# fpc_cable_all.net
KiCad netlist of a schematic drawn in EAGLE
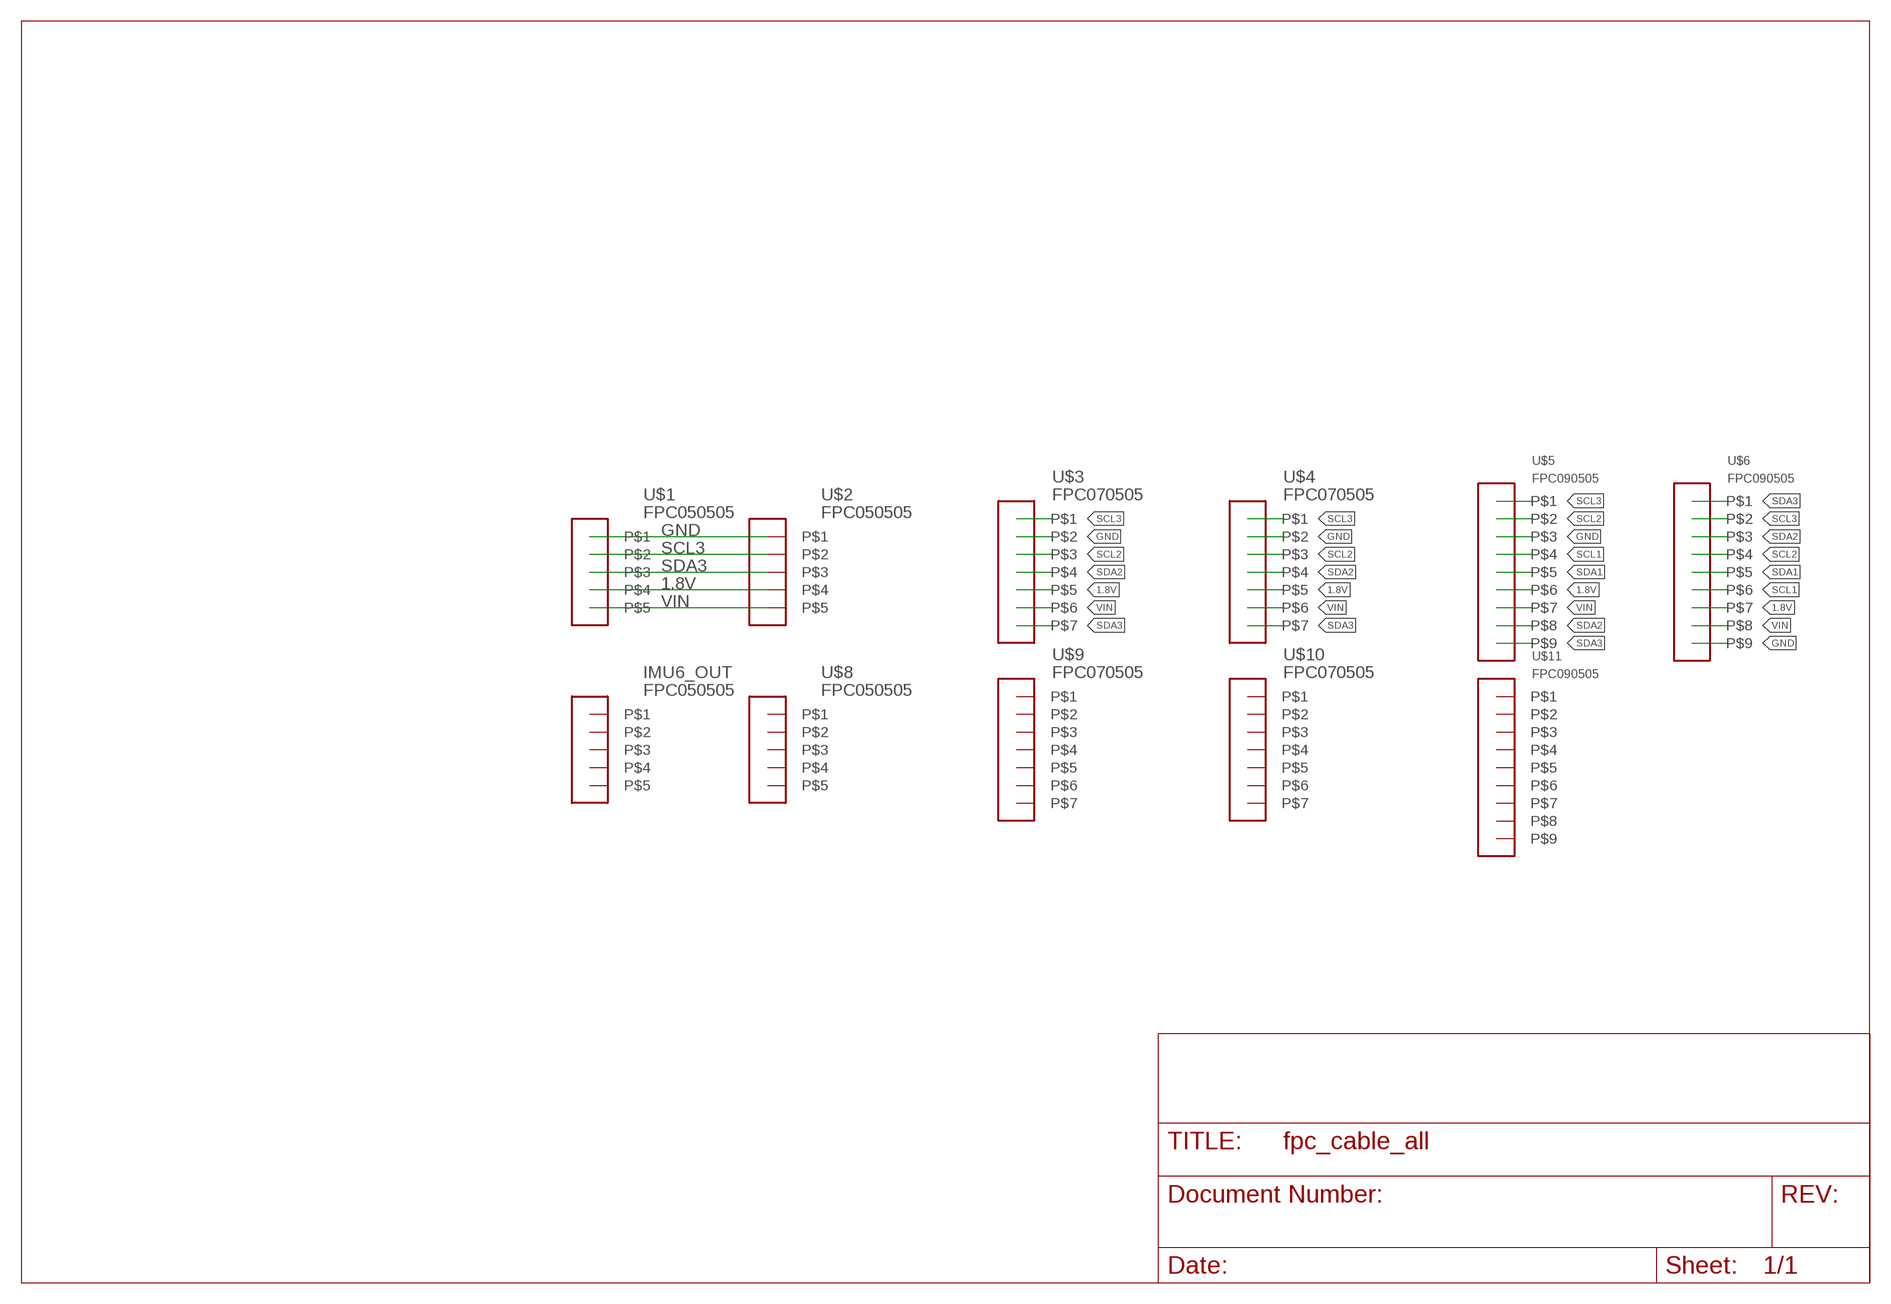
[diagram p0: schematic, sheet 1]

(export (version "E")
  (design (tool "Eeschema 10.0.6"))
  (components
    (comp (ref "IMU6_OUT")
      (value "FPC050505")
      (footprint "eagle-import:FPC0505")
      (libsource (lib "eagle-import") (part "FPC050505"))
    )
    (comp (ref "U$1")
      (value "FPC050505")
      (footprint "eagle-import:FPC0505")
      (libsource (lib "eagle-import") (part "FPC050505"))
    )
    (comp (ref "U$2")
      (value "FPC050505")
      (footprint "eagle-import:FPC0505")
      (libsource (lib "eagle-import") (part "FPC050505"))
    )
    (comp (ref "U$3")
      (value "FPC070505")
      (footprint "eagle-import:FPC0705")
      (libsource (lib "eagle-import") (part "FPC070505"))
    )
    (comp (ref "U$4")
      (value "FPC070505")
      (footprint "eagle-import:FPC0705")
      (libsource (lib "eagle-import") (part "FPC070505"))
    )
    (comp (ref "U$5")
      (value "FPC090505")
      (footprint "eagle-import:FPC0905")
      (libsource (lib "eagle-import") (part "FPC090505"))
    )
    (comp (ref "U$6")
      (value "FPC090505")
      (footprint "eagle-import:FPC0905")
      (libsource (lib "eagle-import") (part "FPC090505"))
    )
    (comp (ref "U$8")
      (value "FPC050505")
      (footprint "eagle-import:FPC0505")
      (libsource (lib "eagle-import") (part "FPC050505"))
    )
    (comp (ref "U$9")
      (value "FPC070505")
      (footprint "eagle-import:FPC0705")
      (libsource (lib "eagle-import") (part "FPC070505"))
    )
    (comp (ref "U$10")
      (value "FPC070505")
      (footprint "eagle-import:FPC0705")
      (libsource (lib "eagle-import") (part "FPC070505"))
    )
    (comp (ref "U$11")
      (value "FPC090505")
      (footprint "eagle-import:FPC0905")
      (libsource (lib "eagle-import") (part "FPC090505"))
    )
  )
  (nets
    (net (code "1") (name "1.8V") (class "Default")
      (node (ref "U$1") (pin "P$4") (pinfunction "P$4_P$4") (pintype "bidirectional"))
      (node (ref "U$2") (pin "P$4") (pinfunction "P$4_P$4") (pintype "bidirectional"))
      (node (ref "U$3") (pin "P$5") (pinfunction "P$5_P$5") (pintype "bidirectional"))
      (node (ref "U$4") (pin "P$5") (pinfunction "P$5_P$5") (pintype "bidirectional"))
      (node (ref "U$5") (pin "P$6") (pinfunction "P$6_P$6") (pintype "bidirectional"))
      (node (ref "U$6") (pin "P$7") (pinfunction "P$7_P$7") (pintype "bidirectional"))
    )
    (net (code "2") (name "GND") (class "Default")
      (node (ref "U$1") (pin "P$1") (pinfunction "P$1_P$1") (pintype "bidirectional"))
      (node (ref "U$2") (pin "P$1") (pinfunction "P$1_P$1") (pintype "bidirectional"))
      (node (ref "U$3") (pin "P$2") (pinfunction "P$2_P$2") (pintype "bidirectional"))
      (node (ref "U$4") (pin "P$2") (pinfunction "P$2_P$2") (pintype "bidirectional"))
      (node (ref "U$5") (pin "P$3") (pinfunction "P$3_P$3") (pintype "bidirectional"))
      (node (ref "U$6") (pin "P$9") (pinfunction "P$9_P$9") (pintype "bidirectional"))
    )
    (net (code "3") (name "SCL1") (class "Default")
      (node (ref "U$5") (pin "P$4") (pinfunction "P$4_P$4") (pintype "bidirectional"))
      (node (ref "U$6") (pin "P$6") (pinfunction "P$6_P$6") (pintype "bidirectional"))
    )
    (net (code "4") (name "SCL2") (class "Default")
      (node (ref "U$3") (pin "P$3") (pinfunction "P$3_P$3") (pintype "bidirectional"))
      (node (ref "U$4") (pin "P$3") (pinfunction "P$3_P$3") (pintype "bidirectional"))
      (node (ref "U$5") (pin "P$2") (pinfunction "P$2_P$2") (pintype "bidirectional"))
      (node (ref "U$6") (pin "P$4") (pinfunction "P$4_P$4") (pintype "bidirectional"))
    )
    (net (code "5") (name "SCL3") (class "Default")
      (node (ref "U$1") (pin "P$2") (pinfunction "P$2_P$2") (pintype "bidirectional"))
      (node (ref "U$2") (pin "P$2") (pinfunction "P$2_P$2") (pintype "bidirectional"))
      (node (ref "U$3") (pin "P$1") (pinfunction "P$1_P$1") (pintype "bidirectional"))
      (node (ref "U$4") (pin "P$1") (pinfunction "P$1_P$1") (pintype "bidirectional"))
      (node (ref "U$5") (pin "P$1") (pinfunction "P$1_P$1") (pintype "bidirectional"))
      (node (ref "U$6") (pin "P$2") (pinfunction "P$2_P$2") (pintype "bidirectional"))
    )
    (net (code "6") (name "SDA1") (class "Default")
      (node (ref "U$5") (pin "P$5") (pinfunction "P$5_P$5") (pintype "bidirectional"))
      (node (ref "U$6") (pin "P$5") (pinfunction "P$5_P$5") (pintype "bidirectional"))
    )
    (net (code "7") (name "SDA2") (class "Default")
      (node (ref "U$3") (pin "P$4") (pinfunction "P$4_P$4") (pintype "bidirectional"))
      (node (ref "U$4") (pin "P$4") (pinfunction "P$4_P$4") (pintype "bidirectional"))
      (node (ref "U$5") (pin "P$8") (pinfunction "P$8_P$8") (pintype "bidirectional"))
      (node (ref "U$6") (pin "P$3") (pinfunction "P$3_P$3") (pintype "bidirectional"))
    )
    (net (code "8") (name "SDA3") (class "Default")
      (node (ref "U$1") (pin "P$3") (pinfunction "P$3_P$3") (pintype "bidirectional"))
      (node (ref "U$2") (pin "P$3") (pinfunction "P$3_P$3") (pintype "bidirectional"))
      (node (ref "U$3") (pin "P$7") (pinfunction "P$7_P$7") (pintype "bidirectional"))
      (node (ref "U$4") (pin "P$7") (pinfunction "P$7_P$7") (pintype "bidirectional"))
      (node (ref "U$5") (pin "P$9") (pinfunction "P$9_P$9") (pintype "bidirectional"))
      (node (ref "U$6") (pin "P$1") (pinfunction "P$1_P$1") (pintype "bidirectional"))
    )
    (net (code "9") (name "VIN") (class "Default")
      (node (ref "U$1") (pin "P$5") (pinfunction "P$5_P$5") (pintype "bidirectional"))
      (node (ref "U$2") (pin "P$5") (pinfunction "P$5_P$5") (pintype "bidirectional"))
      (node (ref "U$3") (pin "P$6") (pinfunction "P$6_P$6") (pintype "bidirectional"))
      (node (ref "U$4") (pin "P$6") (pinfunction "P$6_P$6") (pintype "bidirectional"))
      (node (ref "U$5") (pin "P$7") (pinfunction "P$7_P$7") (pintype "bidirectional"))
      (node (ref "U$6") (pin "P$8") (pinfunction "P$8_P$8") (pintype "bidirectional"))
    )
    (net (code "10") (name "unconnected-(IMU6_OUT-PadP$1)") (class "Default")
      (node (ref "IMU6_OUT") (pin "P$1") (pinfunction "P$1_P$1") (pintype "bidirectional"))
    )
    (net (code "11") (name "unconnected-(IMU6_OUT-PadP$2)") (class "Default")
      (node (ref "IMU6_OUT") (pin "P$2") (pinfunction "P$2_P$2") (pintype "bidirectional"))
    )
    (net (code "12") (name "unconnected-(IMU6_OUT-PadP$3)") (class "Default")
      (node (ref "IMU6_OUT") (pin "P$3") (pinfunction "P$3_P$3") (pintype "bidirectional"))
    )
    (net (code "13") (name "unconnected-(IMU6_OUT-PadP$4)") (class "Default")
      (node (ref "IMU6_OUT") (pin "P$4") (pinfunction "P$4_P$4") (pintype "bidirectional"))
    )
    (net (code "14") (name "unconnected-(IMU6_OUT-PadP$5)") (class "Default")
      (node (ref "IMU6_OUT") (pin "P$5") (pinfunction "P$5_P$5") (pintype "bidirectional"))
    )
    (net (code "15") (name "unconnected-(U$8-PadP$1)") (class "Default")
      (node (ref "U$8") (pin "P$1") (pinfunction "P$1_P$1") (pintype "bidirectional"))
    )
    (net (code "16") (name "unconnected-(U$8-PadP$2)") (class "Default")
      (node (ref "U$8") (pin "P$2") (pinfunction "P$2_P$2") (pintype "bidirectional"))
    )
    (net (code "17") (name "unconnected-(U$8-PadP$3)") (class "Default")
      (node (ref "U$8") (pin "P$3") (pinfunction "P$3_P$3") (pintype "bidirectional"))
    )
    (net (code "18") (name "unconnected-(U$8-PadP$4)") (class "Default")
      (node (ref "U$8") (pin "P$4") (pinfunction "P$4_P$4") (pintype "bidirectional"))
    )
    (net (code "19") (name "unconnected-(U$8-PadP$5)") (class "Default")
      (node (ref "U$8") (pin "P$5") (pinfunction "P$5_P$5") (pintype "bidirectional"))
    )
    (net (code "20") (name "unconnected-(U$9-PadP$1)") (class "Default")
      (node (ref "U$9") (pin "P$1") (pinfunction "P$1_P$1") (pintype "bidirectional"))
    )
    (net (code "21") (name "unconnected-(U$9-PadP$2)") (class "Default")
      (node (ref "U$9") (pin "P$2") (pinfunction "P$2_P$2") (pintype "bidirectional"))
    )
    (net (code "22") (name "unconnected-(U$9-PadP$3)") (class "Default")
      (node (ref "U$9") (pin "P$3") (pinfunction "P$3_P$3") (pintype "bidirectional"))
    )
    (net (code "23") (name "unconnected-(U$9-PadP$4)") (class "Default")
      (node (ref "U$9") (pin "P$4") (pinfunction "P$4_P$4") (pintype "bidirectional"))
    )
    (net (code "24") (name "unconnected-(U$9-PadP$5)") (class "Default")
      (node (ref "U$9") (pin "P$5") (pinfunction "P$5_P$5") (pintype "bidirectional"))
    )
    (net (code "25") (name "unconnected-(U$9-PadP$6)") (class "Default")
      (node (ref "U$9") (pin "P$6") (pinfunction "P$6_P$6") (pintype "bidirectional"))
    )
    (net (code "26") (name "unconnected-(U$9-PadP$7)") (class "Default")
      (node (ref "U$9") (pin "P$7") (pinfunction "P$7_P$7") (pintype "bidirectional"))
    )
    (net (code "27") (name "unconnected-(U$10-PadP$1)") (class "Default")
      (node (ref "U$10") (pin "P$1") (pinfunction "P$1_P$1") (pintype "bidirectional"))
    )
    (net (code "28") (name "unconnected-(U$10-PadP$2)") (class "Default")
      (node (ref "U$10") (pin "P$2") (pinfunction "P$2_P$2") (pintype "bidirectional"))
    )
    (net (code "29") (name "unconnected-(U$10-PadP$3)") (class "Default")
      (node (ref "U$10") (pin "P$3") (pinfunction "P$3_P$3") (pintype "bidirectional"))
    )
    (net (code "30") (name "unconnected-(U$10-PadP$4)") (class "Default")
      (node (ref "U$10") (pin "P$4") (pinfunction "P$4_P$4") (pintype "bidirectional"))
    )
    (net (code "31") (name "unconnected-(U$10-PadP$5)") (class "Default")
      (node (ref "U$10") (pin "P$5") (pinfunction "P$5_P$5") (pintype "bidirectional"))
    )
    (net (code "32") (name "unconnected-(U$10-PadP$6)") (class "Default")
      (node (ref "U$10") (pin "P$6") (pinfunction "P$6_P$6") (pintype "bidirectional"))
    )
    (net (code "33") (name "unconnected-(U$10-PadP$7)") (class "Default")
      (node (ref "U$10") (pin "P$7") (pinfunction "P$7_P$7") (pintype "bidirectional"))
    )
    (net (code "34") (name "unconnected-(U$11-PadP$1)") (class "Default")
      (node (ref "U$11") (pin "P$1") (pinfunction "P$1_P$1") (pintype "bidirectional"))
    )
    (net (code "35") (name "unconnected-(U$11-PadP$2)") (class "Default")
      (node (ref "U$11") (pin "P$2") (pinfunction "P$2_P$2") (pintype "bidirectional"))
    )
    (net (code "36") (name "unconnected-(U$11-PadP$3)") (class "Default")
      (node (ref "U$11") (pin "P$3") (pinfunction "P$3_P$3") (pintype "bidirectional"))
    )
    (net (code "37") (name "unconnected-(U$11-PadP$4)") (class "Default")
      (node (ref "U$11") (pin "P$4") (pinfunction "P$4_P$4") (pintype "bidirectional"))
    )
    (net (code "38") (name "unconnected-(U$11-PadP$5)") (class "Default")
      (node (ref "U$11") (pin "P$5") (pinfunction "P$5_P$5") (pintype "bidirectional"))
    )
    (net (code "39") (name "unconnected-(U$11-PadP$6)") (class "Default")
      (node (ref "U$11") (pin "P$6") (pinfunction "P$6_P$6") (pintype "bidirectional"))
    )
    (net (code "40") (name "unconnected-(U$11-PadP$7)") (class "Default")
      (node (ref "U$11") (pin "P$7") (pinfunction "P$7_P$7") (pintype "bidirectional"))
    )
    (net (code "41") (name "unconnected-(U$11-PadP$8)") (class "Default")
      (node (ref "U$11") (pin "P$8") (pinfunction "P$8_P$8") (pintype "bidirectional"))
    )
    (net (code "42") (name "unconnected-(U$11-PadP$9)") (class "Default")
      (node (ref "U$11") (pin "P$9") (pinfunction "P$9_P$9") (pintype "bidirectional"))
    )
  )
)
